# violed_v2_5.net
KiCad netlist of a schematic drawn in EAGLE
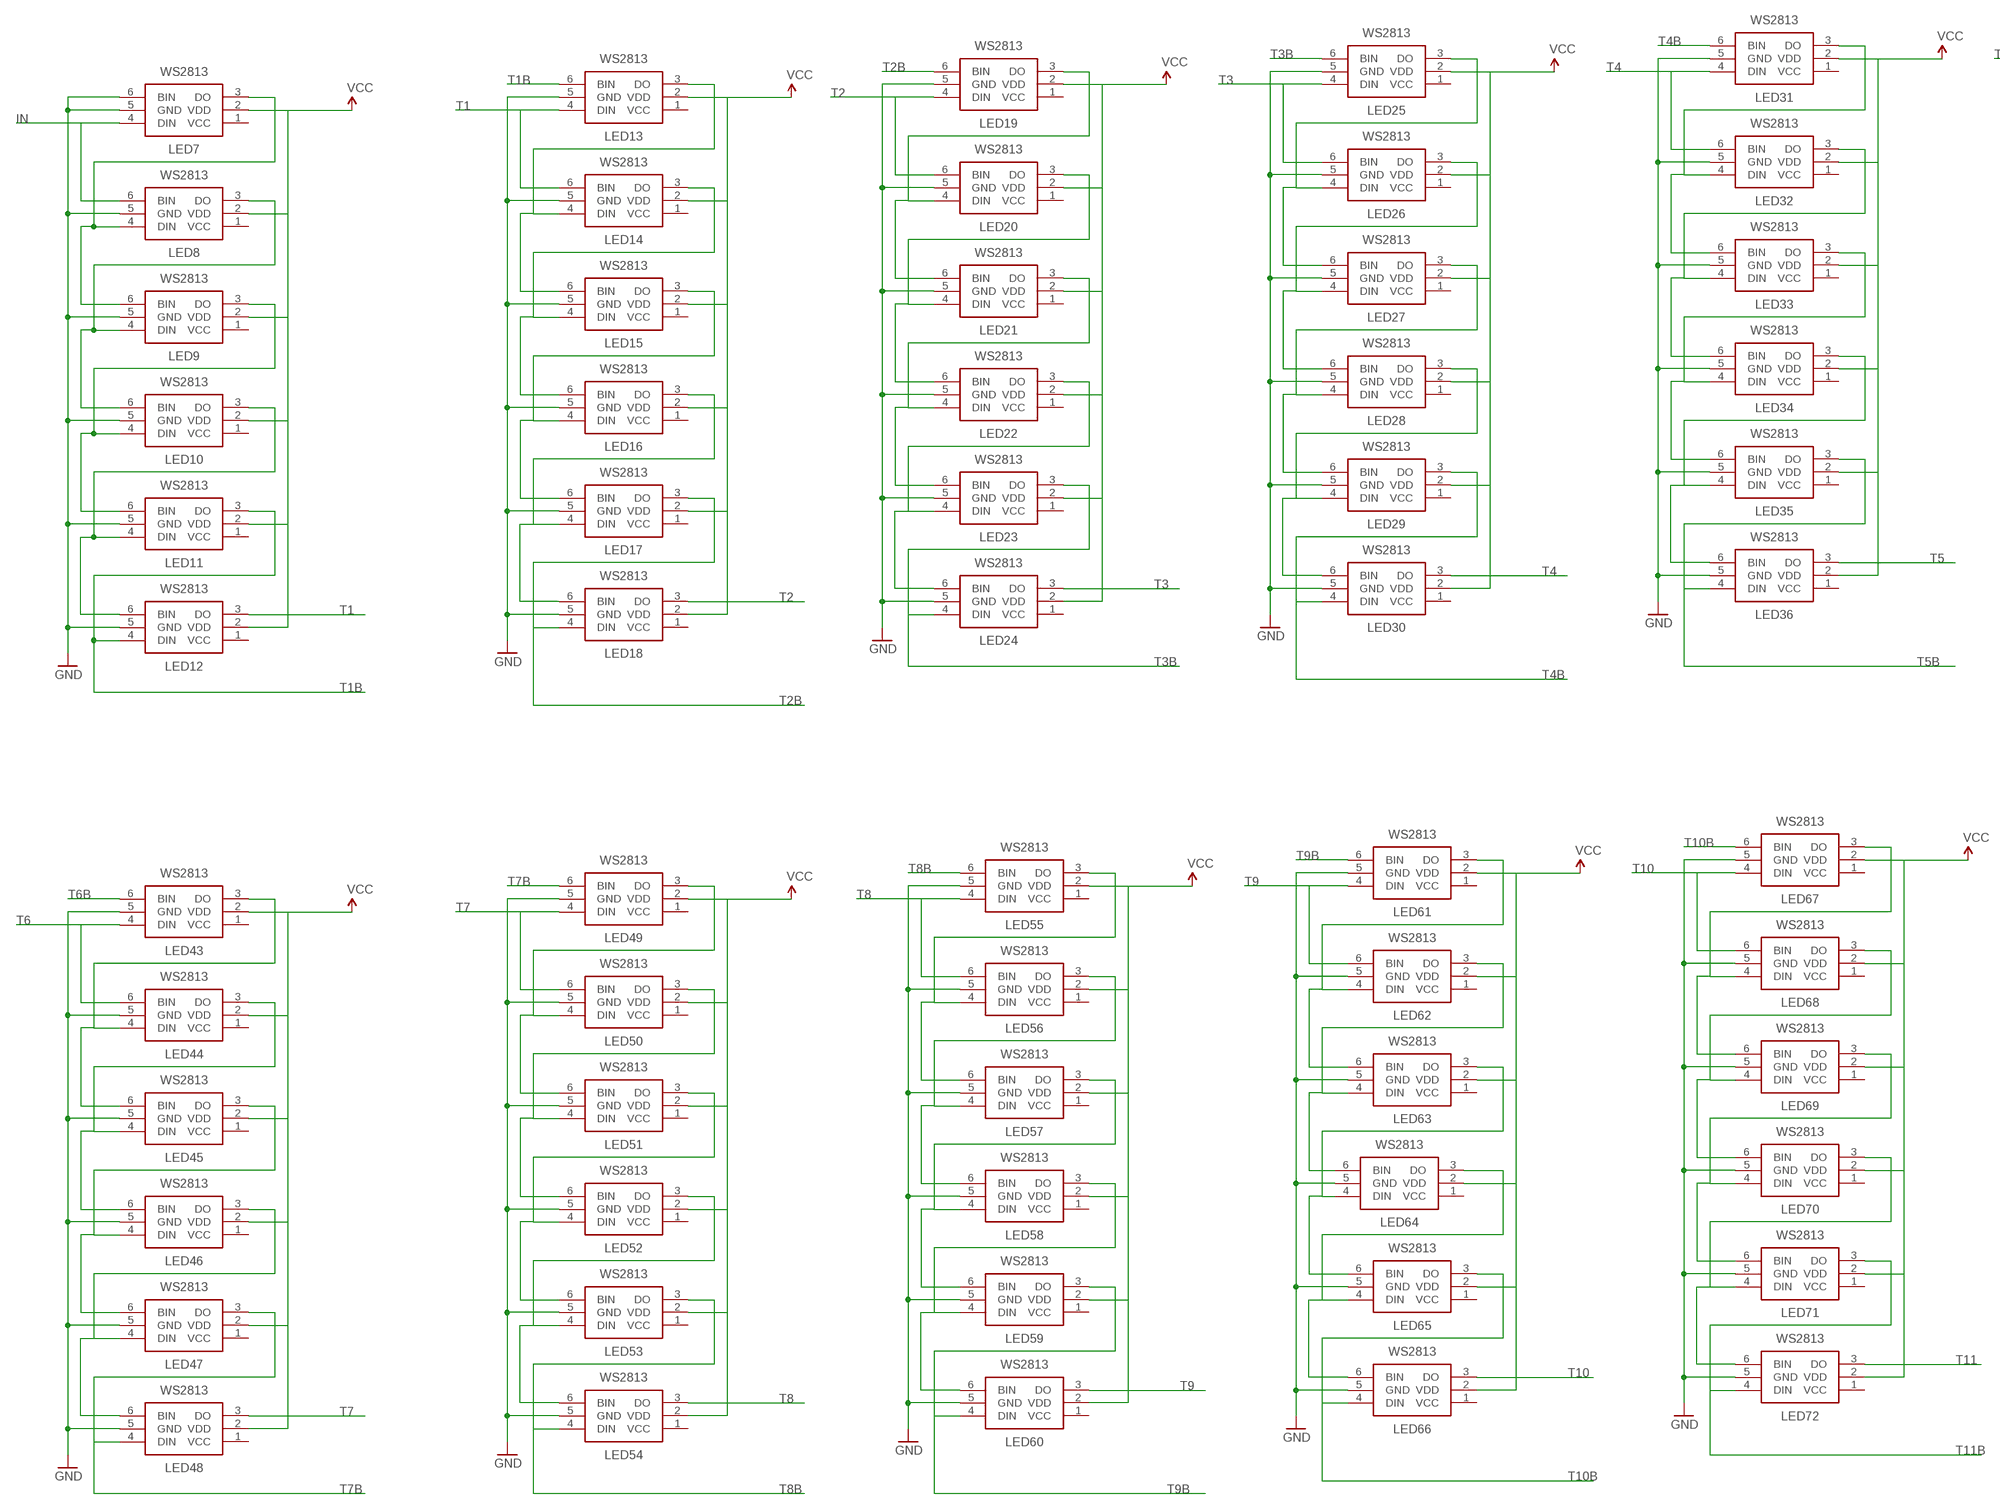
[diagram p0: schematic, sheet 1, part 1 of 2]
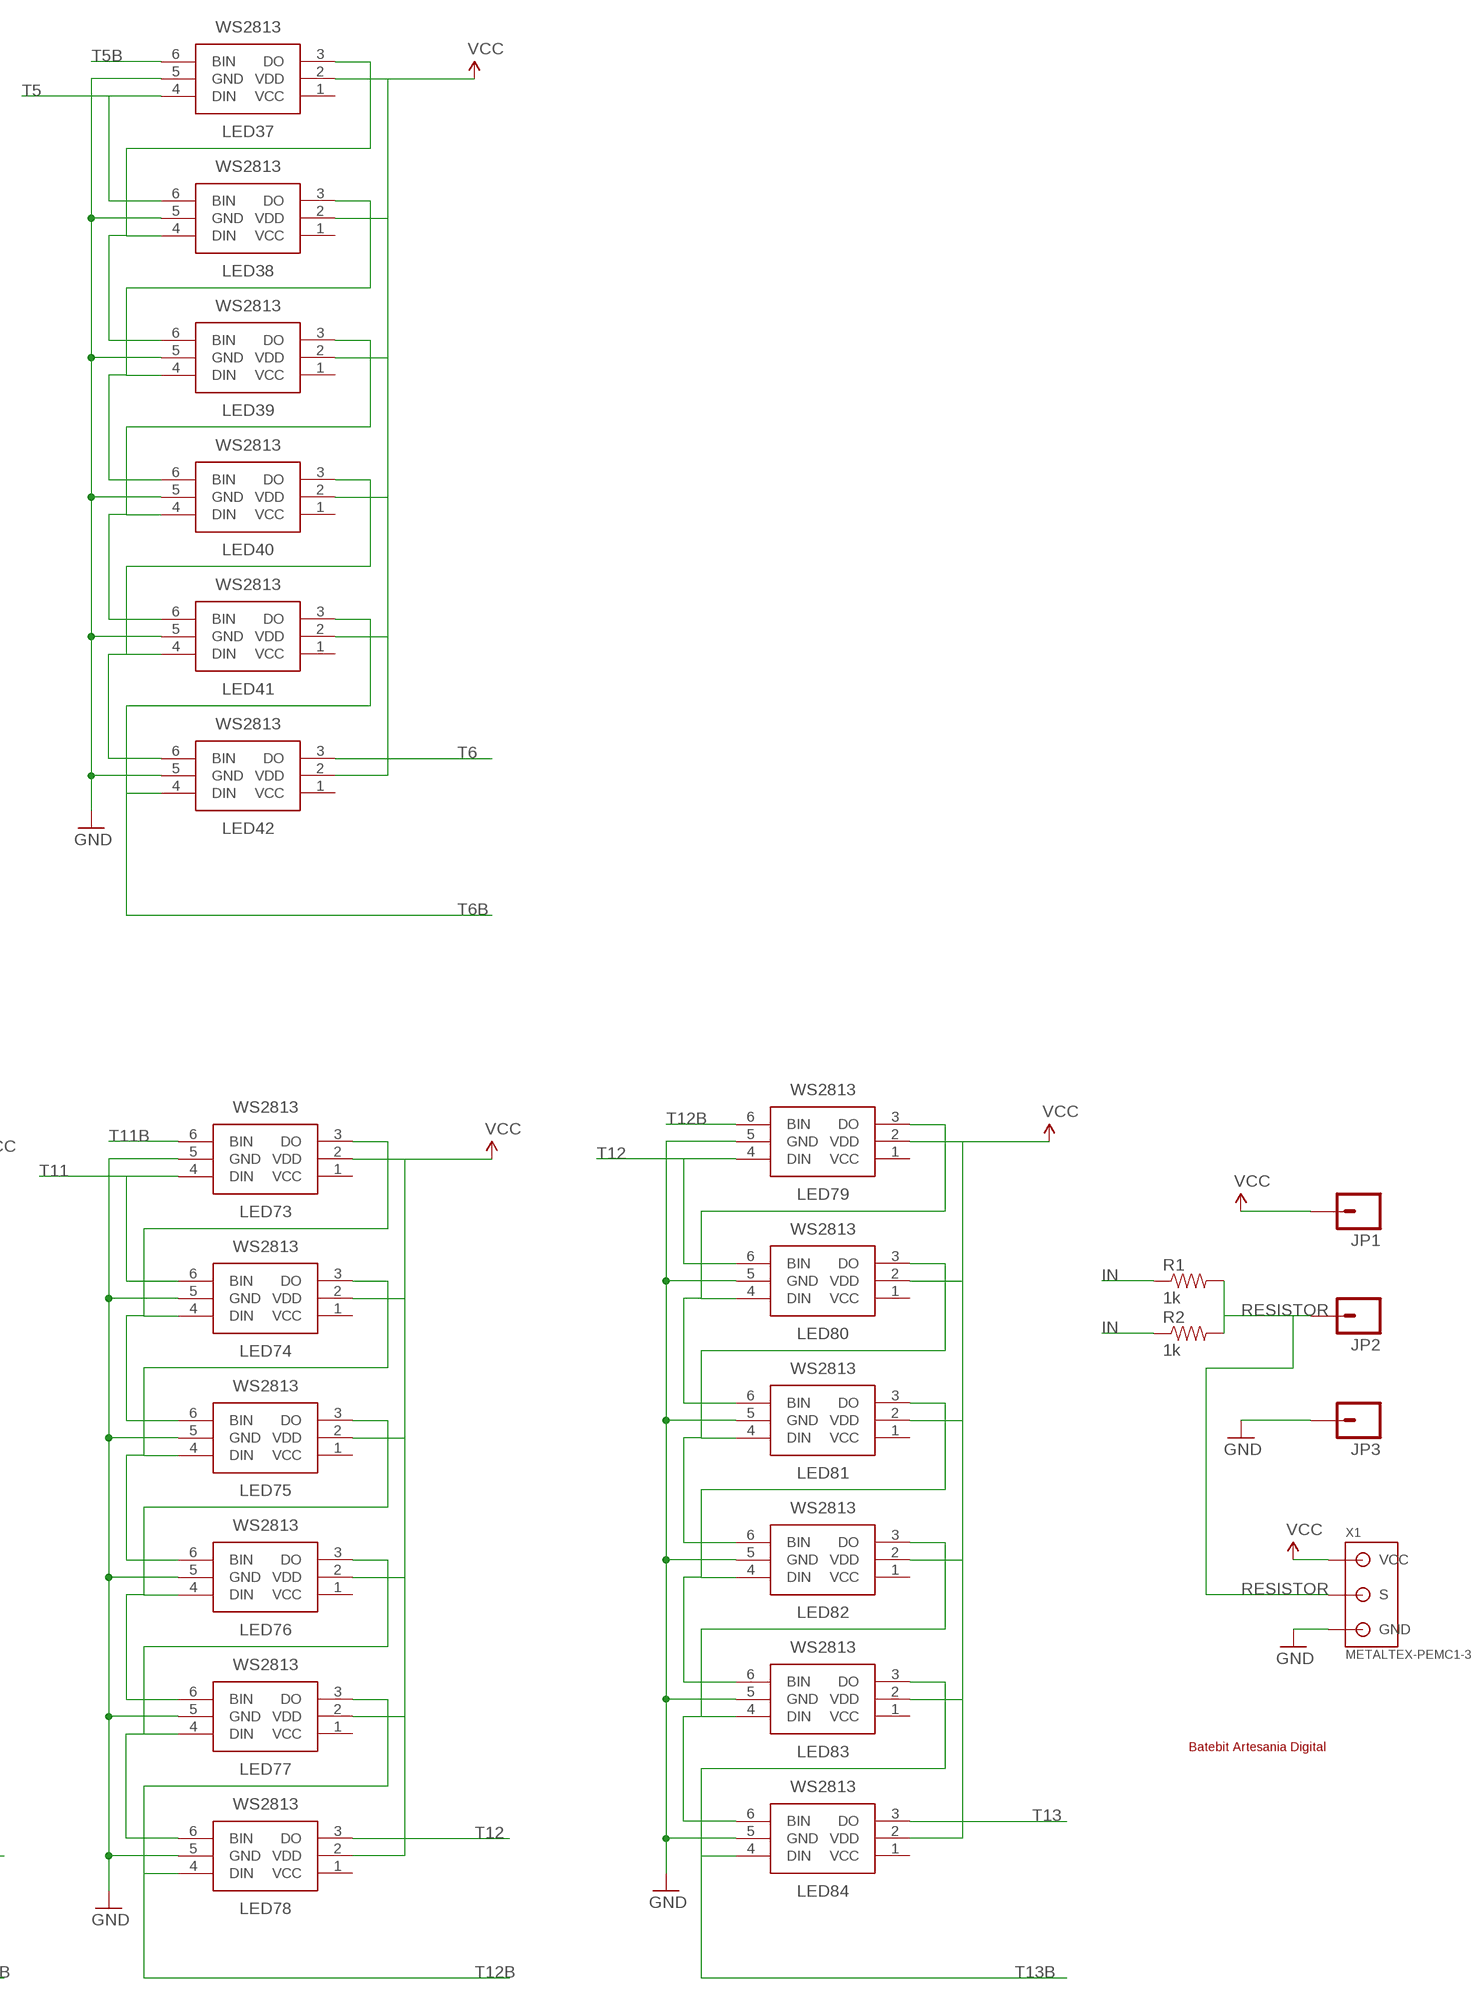
[diagram p1: schematic, sheet 1, part 2 of 2]

(export (version "E")
  (design (tool "Eeschema 10.0.6"))
  (components
    (comp (ref "JP1")
      (value "M01PTH_LONGPAD")
      (footprint "eagle-import:1X01_LONGPAD")
      (libsource (lib "eagle-import") (part "M01PTH_LONGPAD"))
    )
    (comp (ref "JP2")
      (value "M01PTH_LONGPAD")
      (footprint "eagle-import:1X01_LONGPAD")
      (libsource (lib "eagle-import") (part "M01PTH_LONGPAD"))
    )
    (comp (ref "JP3")
      (value "M01PTH_LONGPAD")
      (footprint "eagle-import:1X01_LONGPAD")
      (libsource (lib "eagle-import") (part "M01PTH_LONGPAD"))
    )
    (comp (ref "LED7")
      (value "WS2813")
      (footprint "eagle-import:WS2812")
      (libsource (lib "eagle-import") (part "WS2813"))
    )
    (comp (ref "LED8")
      (value "WS2813")
      (footprint "eagle-import:WS2812")
      (libsource (lib "eagle-import") (part "WS2813"))
    )
    (comp (ref "LED9")
      (value "WS2813")
      (footprint "eagle-import:WS2812")
      (libsource (lib "eagle-import") (part "WS2813"))
    )
    (comp (ref "LED10")
      (value "WS2813")
      (footprint "eagle-import:WS2812")
      (libsource (lib "eagle-import") (part "WS2813"))
    )
    (comp (ref "LED11")
      (value "WS2813")
      (footprint "eagle-import:WS2812")
      (libsource (lib "eagle-import") (part "WS2813"))
    )
    (comp (ref "LED12")
      (value "WS2813")
      (footprint "eagle-import:WS2812")
      (libsource (lib "eagle-import") (part "WS2813"))
    )
    (comp (ref "LED13")
      (value "WS2813")
      (footprint "eagle-import:WS2812")
      (libsource (lib "eagle-import") (part "WS2813"))
    )
    (comp (ref "LED14")
      (value "WS2813")
      (footprint "eagle-import:WS2812")
      (libsource (lib "eagle-import") (part "WS2813"))
    )
    (comp (ref "LED15")
      (value "WS2813")
      (footprint "eagle-import:WS2812")
      (libsource (lib "eagle-import") (part "WS2813"))
    )
    (comp (ref "LED16")
      (value "WS2813")
      (footprint "eagle-import:WS2812")
      (libsource (lib "eagle-import") (part "WS2813"))
    )
    (comp (ref "LED17")
      (value "WS2813")
      (footprint "eagle-import:WS2812")
      (libsource (lib "eagle-import") (part "WS2813"))
    )
    (comp (ref "LED18")
      (value "WS2813")
      (footprint "eagle-import:WS2812")
      (libsource (lib "eagle-import") (part "WS2813"))
    )
    (comp (ref "LED19")
      (value "WS2813")
      (footprint "eagle-import:WS2812")
      (libsource (lib "eagle-import") (part "WS2813"))
    )
    (comp (ref "LED20")
      (value "WS2813")
      (footprint "eagle-import:WS2812")
      (libsource (lib "eagle-import") (part "WS2813"))
    )
    (comp (ref "LED21")
      (value "WS2813")
      (footprint "eagle-import:WS2812")
      (libsource (lib "eagle-import") (part "WS2813"))
    )
    (comp (ref "LED22")
      (value "WS2813")
      (footprint "eagle-import:WS2812")
      (libsource (lib "eagle-import") (part "WS2813"))
    )
    (comp (ref "LED23")
      (value "WS2813")
      (footprint "eagle-import:WS2812")
      (libsource (lib "eagle-import") (part "WS2813"))
    )
    (comp (ref "LED24")
      (value "WS2813")
      (footprint "eagle-import:WS2812")
      (libsource (lib "eagle-import") (part "WS2813"))
    )
    (comp (ref "LED25")
      (value "WS2813")
      (footprint "eagle-import:WS2812")
      (libsource (lib "eagle-import") (part "WS2813"))
    )
    (comp (ref "LED26")
      (value "WS2813")
      (footprint "eagle-import:WS2812")
      (libsource (lib "eagle-import") (part "WS2813"))
    )
    (comp (ref "LED27")
      (value "WS2813")
      (footprint "eagle-import:WS2812")
      (libsource (lib "eagle-import") (part "WS2813"))
    )
    (comp (ref "LED28")
      (value "WS2813")
      (footprint "eagle-import:WS2812")
      (libsource (lib "eagle-import") (part "WS2813"))
    )
    (comp (ref "LED29")
      (value "WS2813")
      (footprint "eagle-import:WS2812")
      (libsource (lib "eagle-import") (part "WS2813"))
    )
    (comp (ref "LED30")
      (value "WS2813")
      (footprint "eagle-import:WS2812")
      (libsource (lib "eagle-import") (part "WS2813"))
    )
    (comp (ref "LED31")
      (value "WS2813")
      (footprint "eagle-import:WS2812")
      (libsource (lib "eagle-import") (part "WS2813"))
    )
    (comp (ref "LED32")
      (value "WS2813")
      (footprint "eagle-import:WS2812")
      (libsource (lib "eagle-import") (part "WS2813"))
    )
    (comp (ref "LED33")
      (value "WS2813")
      (footprint "eagle-import:WS2812")
      (libsource (lib "eagle-import") (part "WS2813"))
    )
    (comp (ref "LED34")
      (value "WS2813")
      (footprint "eagle-import:WS2812")
      (libsource (lib "eagle-import") (part "WS2813"))
    )
    (comp (ref "LED35")
      (value "WS2813")
      (footprint "eagle-import:WS2812")
      (libsource (lib "eagle-import") (part "WS2813"))
    )
    (comp (ref "LED36")
      (value "WS2813")
      (footprint "eagle-import:WS2812")
      (libsource (lib "eagle-import") (part "WS2813"))
    )
    (comp (ref "LED37")
      (value "WS2813")
      (footprint "eagle-import:WS2812")
      (libsource (lib "eagle-import") (part "WS2813"))
    )
    (comp (ref "LED38")
      (value "WS2813")
      (footprint "eagle-import:WS2812")
      (libsource (lib "eagle-import") (part "WS2813"))
    )
    (comp (ref "LED39")
      (value "WS2813")
      (footprint "eagle-import:WS2812")
      (libsource (lib "eagle-import") (part "WS2813"))
    )
    (comp (ref "LED40")
      (value "WS2813")
      (footprint "eagle-import:WS2812")
      (libsource (lib "eagle-import") (part "WS2813"))
    )
    (comp (ref "LED41")
      (value "WS2813")
      (footprint "eagle-import:WS2812")
      (libsource (lib "eagle-import") (part "WS2813"))
    )
    (comp (ref "LED42")
      (value "WS2813")
      (footprint "eagle-import:WS2812")
      (libsource (lib "eagle-import") (part "WS2813"))
    )
    (comp (ref "LED43")
      (value "WS2813")
      (footprint "eagle-import:WS2812")
      (libsource (lib "eagle-import") (part "WS2813"))
    )
    (comp (ref "LED44")
      (value "WS2813")
      (footprint "eagle-import:WS2812")
      (libsource (lib "eagle-import") (part "WS2813"))
    )
    (comp (ref "LED45")
      (value "WS2813")
      (footprint "eagle-import:WS2812")
      (libsource (lib "eagle-import") (part "WS2813"))
    )
    (comp (ref "LED46")
      (value "WS2813")
      (footprint "eagle-import:WS2812")
      (libsource (lib "eagle-import") (part "WS2813"))
    )
    (comp (ref "LED47")
      (value "WS2813")
      (footprint "eagle-import:WS2812")
      (libsource (lib "eagle-import") (part "WS2813"))
    )
    (comp (ref "LED48")
      (value "WS2813")
      (footprint "eagle-import:WS2812")
      (libsource (lib "eagle-import") (part "WS2813"))
    )
    (comp (ref "LED49")
      (value "WS2813")
      (footprint "eagle-import:WS2812")
      (libsource (lib "eagle-import") (part "WS2813"))
    )
    (comp (ref "LED50")
      (value "WS2813")
      (footprint "eagle-import:WS2812")
      (libsource (lib "eagle-import") (part "WS2813"))
    )
    (comp (ref "LED51")
      (value "WS2813")
      (footprint "eagle-import:WS2812")
      (libsource (lib "eagle-import") (part "WS2813"))
    )
    (comp (ref "LED52")
      (value "WS2813")
      (footprint "eagle-import:WS2812")
      (libsource (lib "eagle-import") (part "WS2813"))
    )
    (comp (ref "LED53")
      (value "WS2813")
      (footprint "eagle-import:WS2812")
      (libsource (lib "eagle-import") (part "WS2813"))
    )
    (comp (ref "LED54")
      (value "WS2813")
      (footprint "eagle-import:WS2812")
      (libsource (lib "eagle-import") (part "WS2813"))
    )
    (comp (ref "LED55")
      (value "WS2813")
      (footprint "eagle-import:WS2812")
      (libsource (lib "eagle-import") (part "WS2813"))
    )
    (comp (ref "LED56")
      (value "WS2813")
      (footprint "eagle-import:WS2812")
      (libsource (lib "eagle-import") (part "WS2813"))
    )
    (comp (ref "LED57")
      (value "WS2813")
      (footprint "eagle-import:WS2812")
      (libsource (lib "eagle-import") (part "WS2813"))
    )
    (comp (ref "LED58")
      (value "WS2813")
      (footprint "eagle-import:WS2812")
      (libsource (lib "eagle-import") (part "WS2813"))
    )
    (comp (ref "LED59")
      (value "WS2813")
      (footprint "eagle-import:WS2812")
      (libsource (lib "eagle-import") (part "WS2813"))
    )
    (comp (ref "LED60")
      (value "WS2813")
      (footprint "eagle-import:WS2812")
      (libsource (lib "eagle-import") (part "WS2813"))
    )
    (comp (ref "LED61")
      (value "WS2813")
      (footprint "eagle-import:WS2812")
      (libsource (lib "eagle-import") (part "WS2813"))
    )
    (comp (ref "LED62")
      (value "WS2813")
      (footprint "eagle-import:WS2812")
      (libsource (lib "eagle-import") (part "WS2813"))
    )
    (comp (ref "LED63")
      (value "WS2813")
      (footprint "eagle-import:WS2812")
      (libsource (lib "eagle-import") (part "WS2813"))
    )
    (comp (ref "LED64")
      (value "WS2813")
      (footprint "eagle-import:WS2812")
      (libsource (lib "eagle-import") (part "WS2813"))
    )
    (comp (ref "LED65")
      (value "WS2813")
      (footprint "eagle-import:WS2812")
      (libsource (lib "eagle-import") (part "WS2813"))
    )
    (comp (ref "LED66")
      (value "WS2813")
      (footprint "eagle-import:WS2812")
      (libsource (lib "eagle-import") (part "WS2813"))
    )
    (comp (ref "LED67")
      (value "WS2813")
      (footprint "eagle-import:WS2812")
      (libsource (lib "eagle-import") (part "WS2813"))
    )
    (comp (ref "LED68")
      (value "WS2813")
      (footprint "eagle-import:WS2812")
      (libsource (lib "eagle-import") (part "WS2813"))
    )
    (comp (ref "LED69")
      (value "WS2813")
      (footprint "eagle-import:WS2812")
      (libsource (lib "eagle-import") (part "WS2813"))
    )
    (comp (ref "LED70")
      (value "WS2813")
      (footprint "eagle-import:WS2812")
      (libsource (lib "eagle-import") (part "WS2813"))
    )
    (comp (ref "LED71")
      (value "WS2813")
      (footprint "eagle-import:WS2812")
      (libsource (lib "eagle-import") (part "WS2813"))
    )
    (comp (ref "LED72")
      (value "WS2813")
      (footprint "eagle-import:WS2812")
      (libsource (lib "eagle-import") (part "WS2813"))
    )
    (comp (ref "LED73")
      (value "WS2813")
      (footprint "eagle-import:WS2812")
      (libsource (lib "eagle-import") (part "WS2813"))
    )
    (comp (ref "LED74")
      (value "WS2813")
      (footprint "eagle-import:WS2812")
      (libsource (lib "eagle-import") (part "WS2813"))
    )
    (comp (ref "LED75")
      (value "WS2813")
      (footprint "eagle-import:WS2812")
      (libsource (lib "eagle-import") (part "WS2813"))
    )
    (comp (ref "LED76")
      (value "WS2813")
      (footprint "eagle-import:WS2812")
      (libsource (lib "eagle-import") (part "WS2813"))
    )
    (comp (ref "LED77")
      (value "WS2813")
      (footprint "eagle-import:WS2812")
      (libsource (lib "eagle-import") (part "WS2813"))
    )
    (comp (ref "LED78")
      (value "WS2813")
      (footprint "eagle-import:WS2812")
      (libsource (lib "eagle-import") (part "WS2813"))
    )
    (comp (ref "LED79")
      (value "WS2813")
      (footprint "eagle-import:WS2812")
      (libsource (lib "eagle-import") (part "WS2813"))
    )
    (comp (ref "LED80")
      (value "WS2813")
      (footprint "eagle-import:WS2812")
      (libsource (lib "eagle-import") (part "WS2813"))
    )
    (comp (ref "LED81")
      (value "WS2813")
      (footprint "eagle-import:WS2812")
      (libsource (lib "eagle-import") (part "WS2813"))
    )
    (comp (ref "LED82")
      (value "WS2813")
      (footprint "eagle-import:WS2812")
      (libsource (lib "eagle-import") (part "WS2813"))
    )
    (comp (ref "LED83")
      (value "WS2813")
      (footprint "eagle-import:WS2812")
      (libsource (lib "eagle-import") (part "WS2813"))
    )
    (comp (ref "LED84")
      (value "WS2813")
      (footprint "eagle-import:WS2812")
      (libsource (lib "eagle-import") (part "WS2813"))
    )
    (comp (ref "R1")
      (value "1k")
      (footprint "eagle-import:0805")
      (libsource (lib "eagle-import") (part "RESISTOR0805-RES"))
    )
    (comp (ref "R2")
      (value "1k")
      (footprint "eagle-import:AXIAL-0.4")
      (libsource (lib "eagle-import") (part "RESISTORPTH-1/4W"))
    )
    (comp (ref "U$1")
      (value "BATEBITTOP")
      (footprint "eagle-import:BATEBIT_MED_TOP_LAYER")
      (libsource (lib "eagle-import") (part "BATEBITTOP"))
    )
    (comp (ref "X1")
      (value "METALTEX-PEMC1-3")
      (footprint "eagle-import:METALTEX-PEMC1-3-PACKAGE-LONG-PAD")
      (libsource (lib "eagle-import") (part "METALTEX-PEMC1-3"))
    )
  )
  (nets
    (net (code "1") (name "/IN") (class "Default")
      (node (ref "LED7") (pin "4") (pinfunction "DIN_4") (pintype "passive"))
      (node (ref "LED8") (pin "6") (pinfunction "BIN_6") (pintype "passive"))
      (node (ref "R1") (pin "1") (pinfunction "1_1") (pintype "passive"))
      (node (ref "R2") (pin "P$1") (pinfunction "1_P$1") (pintype "passive"))
    )
    (net (code "2") (name "/RESISTOR") (class "Default")
      (node (ref "JP2") (pin "1") (pinfunction "1_1") (pintype "passive"))
      (node (ref "R1") (pin "2") (pinfunction "2_2") (pintype "passive"))
      (node (ref "R2") (pin "P$2") (pinfunction "2_P$2") (pintype "passive"))
      (node (ref "X1") (pin "2") (pinfunction "S_2") (pintype "bidirectional"))
    )
    (net (code "3") (name "/T1") (class "Default")
      (node (ref "LED12") (pin "3") (pinfunction "DO_3") (pintype "passive"))
      (node (ref "LED13") (pin "4") (pinfunction "DIN_4") (pintype "passive"))
      (node (ref "LED14") (pin "6") (pinfunction "BIN_6") (pintype "passive"))
    )
    (net (code "4") (name "/T1B") (class "Default")
      (node (ref "LED11") (pin "3") (pinfunction "DO_3") (pintype "passive"))
      (node (ref "LED12") (pin "4") (pinfunction "DIN_4") (pintype "passive"))
      (node (ref "LED13") (pin "6") (pinfunction "BIN_6") (pintype "passive"))
    )
    (net (code "5") (name "/T2") (class "Default")
      (node (ref "LED18") (pin "3") (pinfunction "DO_3") (pintype "passive"))
      (node (ref "LED19") (pin "4") (pinfunction "DIN_4") (pintype "passive"))
      (node (ref "LED20") (pin "6") (pinfunction "BIN_6") (pintype "passive"))
    )
    (net (code "6") (name "/T2B") (class "Default")
      (node (ref "LED17") (pin "3") (pinfunction "DO_3") (pintype "passive"))
      (node (ref "LED18") (pin "4") (pinfunction "DIN_4") (pintype "passive"))
      (node (ref "LED19") (pin "6") (pinfunction "BIN_6") (pintype "passive"))
    )
    (net (code "7") (name "/T3") (class "Default")
      (node (ref "LED24") (pin "3") (pinfunction "DO_3") (pintype "passive"))
      (node (ref "LED25") (pin "4") (pinfunction "DIN_4") (pintype "passive"))
      (node (ref "LED26") (pin "6") (pinfunction "BIN_6") (pintype "passive"))
    )
    (net (code "8") (name "/T3B") (class "Default")
      (node (ref "LED23") (pin "3") (pinfunction "DO_3") (pintype "passive"))
      (node (ref "LED24") (pin "4") (pinfunction "DIN_4") (pintype "passive"))
      (node (ref "LED25") (pin "6") (pinfunction "BIN_6") (pintype "passive"))
    )
    (net (code "9") (name "/T4") (class "Default")
      (node (ref "LED30") (pin "3") (pinfunction "DO_3") (pintype "passive"))
      (node (ref "LED31") (pin "4") (pinfunction "DIN_4") (pintype "passive"))
      (node (ref "LED32") (pin "6") (pinfunction "BIN_6") (pintype "passive"))
    )
    (net (code "10") (name "/T4B") (class "Default")
      (node (ref "LED29") (pin "3") (pinfunction "DO_3") (pintype "passive"))
      (node (ref "LED30") (pin "4") (pinfunction "DIN_4") (pintype "passive"))
      (node (ref "LED31") (pin "6") (pinfunction "BIN_6") (pintype "passive"))
    )
    (net (code "11") (name "/T5") (class "Default")
      (node (ref "LED36") (pin "3") (pinfunction "DO_3") (pintype "passive"))
      (node (ref "LED37") (pin "4") (pinfunction "DIN_4") (pintype "passive"))
      (node (ref "LED38") (pin "6") (pinfunction "BIN_6") (pintype "passive"))
    )
    (net (code "12") (name "/T5B") (class "Default")
      (node (ref "LED35") (pin "3") (pinfunction "DO_3") (pintype "passive"))
      (node (ref "LED36") (pin "4") (pinfunction "DIN_4") (pintype "passive"))
      (node (ref "LED37") (pin "6") (pinfunction "BIN_6") (pintype "passive"))
    )
    (net (code "13") (name "/T6") (class "Default")
      (node (ref "LED42") (pin "3") (pinfunction "DO_3") (pintype "passive"))
      (node (ref "LED43") (pin "4") (pinfunction "DIN_4") (pintype "passive"))
      (node (ref "LED44") (pin "6") (pinfunction "BIN_6") (pintype "passive"))
    )
    (net (code "14") (name "/T6B") (class "Default")
      (node (ref "LED41") (pin "3") (pinfunction "DO_3") (pintype "passive"))
      (node (ref "LED42") (pin "4") (pinfunction "DIN_4") (pintype "passive"))
      (node (ref "LED43") (pin "6") (pinfunction "BIN_6") (pintype "passive"))
    )
    (net (code "15") (name "/T7") (class "Default")
      (node (ref "LED48") (pin "3") (pinfunction "DO_3") (pintype "passive"))
      (node (ref "LED49") (pin "4") (pinfunction "DIN_4") (pintype "passive"))
      (node (ref "LED50") (pin "6") (pinfunction "BIN_6") (pintype "passive"))
    )
    (net (code "16") (name "/T7B") (class "Default")
      (node (ref "LED47") (pin "3") (pinfunction "DO_3") (pintype "passive"))
      (node (ref "LED48") (pin "4") (pinfunction "DIN_4") (pintype "passive"))
      (node (ref "LED49") (pin "6") (pinfunction "BIN_6") (pintype "passive"))
    )
    (net (code "17") (name "/T8") (class "Default")
      (node (ref "LED54") (pin "3") (pinfunction "DO_3") (pintype "passive"))
      (node (ref "LED55") (pin "4") (pinfunction "DIN_4") (pintype "passive"))
      (node (ref "LED56") (pin "6") (pinfunction "BIN_6") (pintype "passive"))
    )
    (net (code "18") (name "/T8B") (class "Default")
      (node (ref "LED53") (pin "3") (pinfunction "DO_3") (pintype "passive"))
      (node (ref "LED54") (pin "4") (pinfunction "DIN_4") (pintype "passive"))
      (node (ref "LED55") (pin "6") (pinfunction "BIN_6") (pintype "passive"))
    )
    (net (code "19") (name "/T9") (class "Default")
      (node (ref "LED60") (pin "3") (pinfunction "DO_3") (pintype "passive"))
      (node (ref "LED61") (pin "4") (pinfunction "DIN_4") (pintype "passive"))
      (node (ref "LED62") (pin "6") (pinfunction "BIN_6") (pintype "passive"))
    )
    (net (code "20") (name "/T9B") (class "Default")
      (node (ref "LED59") (pin "3") (pinfunction "DO_3") (pintype "passive"))
      (node (ref "LED60") (pin "4") (pinfunction "DIN_4") (pintype "passive"))
      (node (ref "LED61") (pin "6") (pinfunction "BIN_6") (pintype "passive"))
    )
    (net (code "21") (name "/T10") (class "Default")
      (node (ref "LED66") (pin "3") (pinfunction "DO_3") (pintype "passive"))
      (node (ref "LED67") (pin "4") (pinfunction "DIN_4") (pintype "passive"))
      (node (ref "LED68") (pin "6") (pinfunction "BIN_6") (pintype "passive"))
    )
    (net (code "22") (name "/T10B") (class "Default")
      (node (ref "LED65") (pin "3") (pinfunction "DO_3") (pintype "passive"))
      (node (ref "LED66") (pin "4") (pinfunction "DIN_4") (pintype "passive"))
      (node (ref "LED67") (pin "6") (pinfunction "BIN_6") (pintype "passive"))
    )
    (net (code "23") (name "/T11") (class "Default")
      (node (ref "LED72") (pin "3") (pinfunction "DO_3") (pintype "passive"))
      (node (ref "LED73") (pin "4") (pinfunction "DIN_4") (pintype "passive"))
      (node (ref "LED74") (pin "6") (pinfunction "BIN_6") (pintype "passive"))
    )
    (net (code "24") (name "/T11B") (class "Default")
      (node (ref "LED71") (pin "3") (pinfunction "DO_3") (pintype "passive"))
      (node (ref "LED72") (pin "4") (pinfunction "DIN_4") (pintype "passive"))
      (node (ref "LED73") (pin "6") (pinfunction "BIN_6") (pintype "passive"))
    )
    (net (code "25") (name "/T12") (class "Default")
      (node (ref "LED78") (pin "3") (pinfunction "DO_3") (pintype "passive"))
      (node (ref "LED79") (pin "4") (pinfunction "DIN_4") (pintype "passive"))
      (node (ref "LED80") (pin "6") (pinfunction "BIN_6") (pintype "passive"))
    )
    (net (code "26") (name "/T12B") (class "Default")
      (node (ref "LED77") (pin "3") (pinfunction "DO_3") (pintype "passive"))
      (node (ref "LED78") (pin "4") (pinfunction "DIN_4") (pintype "passive"))
      (node (ref "LED79") (pin "6") (pinfunction "BIN_6") (pintype "passive"))
    )
    (net (code "27") (name "/T13") (class "Default")
      (node (ref "LED84") (pin "3") (pinfunction "DO_3") (pintype "passive"))
    )
    (net (code "28") (name "/T13B") (class "Default")
      (node (ref "LED83") (pin "3") (pinfunction "DO_3") (pintype "passive"))
      (node (ref "LED84") (pin "4") (pinfunction "DIN_4") (pintype "passive"))
    )
    (net (code "29") (name "GND") (class "Default")
      (node (ref "JP3") (pin "1") (pinfunction "1_1") (pintype "passive"))
      (node (ref "LED10") (pin "5") (pinfunction "GND_5") (pintype "passive"))
      (node (ref "LED11") (pin "5") (pinfunction "GND_5") (pintype "passive"))
      (node (ref "LED12") (pin "5") (pinfunction "GND_5") (pintype "passive"))
      (node (ref "LED13") (pin "5") (pinfunction "GND_5") (pintype "passive"))
      (node (ref "LED14") (pin "5") (pinfunction "GND_5") (pintype "passive"))
      (node (ref "LED15") (pin "5") (pinfunction "GND_5") (pintype "passive"))
      (node (ref "LED16") (pin "5") (pinfunction "GND_5") (pintype "passive"))
      (node (ref "LED17") (pin "5") (pinfunction "GND_5") (pintype "passive"))
      (node (ref "LED18") (pin "5") (pinfunction "GND_5") (pintype "passive"))
      (node (ref "LED19") (pin "5") (pinfunction "GND_5") (pintype "passive"))
      (node (ref "LED20") (pin "5") (pinfunction "GND_5") (pintype "passive"))
      (node (ref "LED21") (pin "5") (pinfunction "GND_5") (pintype "passive"))
      (node (ref "LED22") (pin "5") (pinfunction "GND_5") (pintype "passive"))
      (node (ref "LED23") (pin "5") (pinfunction "GND_5") (pintype "passive"))
      (node (ref "LED24") (pin "5") (pinfunction "GND_5") (pintype "passive"))
      (node (ref "LED25") (pin "5") (pinfunction "GND_5") (pintype "passive"))
      (node (ref "LED26") (pin "5") (pinfunction "GND_5") (pintype "passive"))
      (node (ref "LED27") (pin "5") (pinfunction "GND_5") (pintype "passive"))
      (node (ref "LED28") (pin "5") (pinfunction "GND_5") (pintype "passive"))
      (node (ref "LED29") (pin "5") (pinfunction "GND_5") (pintype "passive"))
      (node (ref "LED30") (pin "5") (pinfunction "GND_5") (pintype "passive"))
      (node (ref "LED31") (pin "5") (pinfunction "GND_5") (pintype "passive"))
      (node (ref "LED32") (pin "5") (pinfunction "GND_5") (pintype "passive"))
      (node (ref "LED33") (pin "5") (pinfunction "GND_5") (pintype "passive"))
      (node (ref "LED34") (pin "5") (pinfunction "GND_5") (pintype "passive"))
      (node (ref "LED35") (pin "5") (pinfunction "GND_5") (pintype "passive"))
      (node (ref "LED36") (pin "5") (pinfunction "GND_5") (pintype "passive"))
      (node (ref "LED37") (pin "5") (pinfunction "GND_5") (pintype "passive"))
      (node (ref "LED38") (pin "5") (pinfunction "GND_5") (pintype "passive"))
      (node (ref "LED39") (pin "5") (pinfunction "GND_5") (pintype "passive"))
      (node (ref "LED40") (pin "5") (pinfunction "GND_5") (pintype "passive"))
      (node (ref "LED41") (pin "5") (pinfunction "GND_5") (pintype "passive"))
      (node (ref "LED42") (pin "5") (pinfunction "GND_5") (pintype "passive"))
      (node (ref "LED43") (pin "5") (pinfunction "GND_5") (pintype "passive"))
      (node (ref "LED44") (pin "5") (pinfunction "GND_5") (pintype "passive"))
      (node (ref "LED45") (pin "5") (pinfunction "GND_5") (pintype "passive"))
      (node (ref "LED46") (pin "5") (pinfunction "GND_5") (pintype "passive"))
      (node (ref "LED47") (pin "5") (pinfunction "GND_5") (pintype "passive"))
      (node (ref "LED48") (pin "5") (pinfunction "GND_5") (pintype "passive"))
      (node (ref "LED49") (pin "5") (pinfunction "GND_5") (pintype "passive"))
      (node (ref "LED50") (pin "5") (pinfunction "GND_5") (pintype "passive"))
      (node (ref "LED51") (pin "5") (pinfunction "GND_5") (pintype "passive"))
      (node (ref "LED52") (pin "5") (pinfunction "GND_5") (pintype "passive"))
      (node (ref "LED53") (pin "5") (pinfunction "GND_5") (pintype "passive"))
      (node (ref "LED54") (pin "5") (pinfunction "GND_5") (pintype "passive"))
      (node (ref "LED55") (pin "5") (pinfunction "GND_5") (pintype "passive"))
      (node (ref "LED56") (pin "5") (pinfunction "GND_5") (pintype "passive"))
      (node (ref "LED57") (pin "5") (pinfunction "GND_5") (pintype "passive"))
      (node (ref "LED58") (pin "5") (pinfunction "GND_5") (pintype "passive"))
      (node (ref "LED59") (pin "5") (pinfunction "GND_5") (pintype "passive"))
      (node (ref "LED60") (pin "5") (pinfunction "GND_5") (pintype "passive"))
      (node (ref "LED61") (pin "5") (pinfunction "GND_5") (pintype "passive"))
      (node (ref "LED62") (pin "5") (pinfunction "GND_5") (pintype "passive"))
      (node (ref "LED63") (pin "5") (pinfunction "GND_5") (pintype "passive"))
      (node (ref "LED64") (pin "5") (pinfunction "GND_5") (pintype "passive"))
      (node (ref "LED65") (pin "5") (pinfunction "GND_5") (pintype "passive"))
      (node (ref "LED66") (pin "5") (pinfunction "GND_5") (pintype "passive"))
      (node (ref "LED67") (pin "5") (pinfunction "GND_5") (pintype "passive"))
      (node (ref "LED68") (pin "5") (pinfunction "GND_5") (pintype "passive"))
      (node (ref "LED69") (pin "5") (pinfunction "GND_5") (pintype "passive"))
      (node (ref "LED7") (pin "5") (pinfunction "GND_5") (pintype "passive"))
      (node (ref "LED7") (pin "6") (pinfunction "BIN_6") (pintype "passive"))
      (node (ref "LED70") (pin "5") (pinfunction "GND_5") (pintype "passive"))
      (node (ref "LED71") (pin "5") (pinfunction "GND_5") (pintype "passive"))
      (node (ref "LED72") (pin "5") (pinfunction "GND_5") (pintype "passive"))
      (node (ref "LED73") (pin "5") (pinfunction "GND_5") (pintype "passive"))
      (node (ref "LED74") (pin "5") (pinfunction "GND_5") (pintype "passive"))
      (node (ref "LED75") (pin "5") (pinfunction "GND_5") (pintype "passive"))
      (node (ref "LED76") (pin "5") (pinfunction "GND_5") (pintype "passive"))
      (node (ref "LED77") (pin "5") (pinfunction "GND_5") (pintype "passive"))
      (node (ref "LED78") (pin "5") (pinfunction "GND_5") (pintype "passive"))
      (node (ref "LED79") (pin "5") (pinfunction "GND_5") (pintype "passive"))
      (node (ref "LED8") (pin "5") (pinfunction "GND_5") (pintype "passive"))
      (node (ref "LED80") (pin "5") (pinfunction "GND_5") (pintype "passive"))
      (node (ref "LED81") (pin "5") (pinfunction "GND_5") (pintype "passive"))
      (node (ref "LED82") (pin "5") (pinfunction "GND_5") (pintype "passive"))
      (node (ref "LED83") (pin "5") (pinfunction "GND_5") (pintype "passive"))
      (node (ref "LED84") (pin "5") (pinfunction "GND_5") (pintype "passive"))
      (node (ref "LED9") (pin "5") (pinfunction "GND_5") (pintype "passive"))
      (node (ref "X1") (pin "1") (pinfunction "GND_1") (pintype "bidirectional"))
    )
    (net (code "30") (name "Net-(LED7-DO)") (class "Default")
      (node (ref "LED7") (pin "3") (pinfunction "DO_3") (pintype "passive"))
      (node (ref "LED8") (pin "4") (pinfunction "DIN_4") (pintype "passive"))
      (node (ref "LED9") (pin "6") (pinfunction "BIN_6") (pintype "passive"))
    )
    (net (code "31") (name "Net-(LED10-BIN)") (class "Default")
      (node (ref "LED10") (pin "6") (pinfunction "BIN_6") (pintype "passive"))
      (node (ref "LED8") (pin "3") (pinfunction "DO_3") (pintype "passive"))
      (node (ref "LED9") (pin "4") (pinfunction "DIN_4") (pintype "passive"))
    )
    (net (code "32") (name "Net-(LED10-DIN)") (class "Default")
      (node (ref "LED10") (pin "4") (pinfunction "DIN_4") (pintype "passive"))
      (node (ref "LED11") (pin "6") (pinfunction "BIN_6") (pintype "passive"))
      (node (ref "LED9") (pin "3") (pinfunction "DO_3") (pintype "passive"))
    )
    (net (code "33") (name "Net-(LED10-DO)") (class "Default")
      (node (ref "LED10") (pin "3") (pinfunction "DO_3") (pintype "passive"))
      (node (ref "LED11") (pin "4") (pinfunction "DIN_4") (pintype "passive"))
      (node (ref "LED12") (pin "6") (pinfunction "BIN_6") (pintype "passive"))
    )
    (net (code "34") (name "Net-(LED13-DO)") (class "Default")
      (node (ref "LED13") (pin "3") (pinfunction "DO_3") (pintype "passive"))
      (node (ref "LED14") (pin "4") (pinfunction "DIN_4") (pintype "passive"))
      (node (ref "LED15") (pin "6") (pinfunction "BIN_6") (pintype "passive"))
    )
    (net (code "35") (name "Net-(LED14-DO)") (class "Default")
      (node (ref "LED14") (pin "3") (pinfunction "DO_3") (pintype "passive"))
      (node (ref "LED15") (pin "4") (pinfunction "DIN_4") (pintype "passive"))
      (node (ref "LED16") (pin "6") (pinfunction "BIN_6") (pintype "passive"))
    )
    (net (code "36") (name "Net-(LED15-DO)") (class "Default")
      (node (ref "LED15") (pin "3") (pinfunction "DO_3") (pintype "passive"))
      (node (ref "LED16") (pin "4") (pinfunction "DIN_4") (pintype "passive"))
      (node (ref "LED17") (pin "6") (pinfunction "BIN_6") (pintype "passive"))
    )
    (net (code "37") (name "Net-(LED16-DO)") (class "Default")
      (node (ref "LED16") (pin "3") (pinfunction "DO_3") (pintype "passive"))
      (node (ref "LED17") (pin "4") (pinfunction "DIN_4") (pintype "passive"))
      (node (ref "LED18") (pin "6") (pinfunction "BIN_6") (pintype "passive"))
    )
    (net (code "38") (name "Net-(LED19-DO)") (class "Default")
      (node (ref "LED19") (pin "3") (pinfunction "DO_3") (pintype "passive"))
      (node (ref "LED20") (pin "4") (pinfunction "DIN_4") (pintype "passive"))
      (node (ref "LED21") (pin "6") (pinfunction "BIN_6") (pintype "passive"))
    )
    (net (code "39") (name "Net-(LED20-DO)") (class "Default")
      (node (ref "LED20") (pin "3") (pinfunction "DO_3") (pintype "passive"))
      (node (ref "LED21") (pin "4") (pinfunction "DIN_4") (pintype "passive"))
      (node (ref "LED22") (pin "6") (pinfunction "BIN_6") (pintype "passive"))
    )
    (net (code "40") (name "Net-(LED21-DO)") (class "Default")
      (node (ref "LED21") (pin "3") (pinfunction "DO_3") (pintype "passive"))
      (node (ref "LED22") (pin "4") (pinfunction "DIN_4") (pintype "passive"))
      (node (ref "LED23") (pin "6") (pinfunction "BIN_6") (pintype "passive"))
    )
    (net (code "41") (name "Net-(LED22-DO)") (class "Default")
      (node (ref "LED22") (pin "3") (pinfunction "DO_3") (pintype "passive"))
      (node (ref "LED23") (pin "4") (pinfunction "DIN_4") (pintype "passive"))
      (node (ref "LED24") (pin "6") (pinfunction "BIN_6") (pintype "passive"))
    )
    (net (code "42") (name "Net-(LED25-DO)") (class "Default")
      (node (ref "LED25") (pin "3") (pinfunction "DO_3") (pintype "passive"))
      (node (ref "LED26") (pin "4") (pinfunction "DIN_4") (pintype "passive"))
      (node (ref "LED27") (pin "6") (pinfunction "BIN_6") (pintype "passive"))
    )
    (net (code "43") (name "Net-(LED26-DO)") (class "Default")
      (node (ref "LED26") (pin "3") (pinfunction "DO_3") (pintype "passive"))
      (node (ref "LED27") (pin "4") (pinfunction "DIN_4") (pintype "passive"))
      (node (ref "LED28") (pin "6") (pinfunction "BIN_6") (pintype "passive"))
    )
    (net (code "44") (name "Net-(LED27-DO)") (class "Default")
      (node (ref "LED27") (pin "3") (pinfunction "DO_3") (pintype "passive"))
      (node (ref "LED28") (pin "4") (pinfunction "DIN_4") (pintype "passive"))
      (node (ref "LED29") (pin "6") (pinfunction "BIN_6") (pintype "passive"))
    )
    (net (code "45") (name "Net-(LED28-DO)") (class "Default")
      (node (ref "LED28") (pin "3") (pinfunction "DO_3") (pintype "passive"))
      (node (ref "LED29") (pin "4") (pinfunction "DIN_4") (pintype "passive"))
      (node (ref "LED30") (pin "6") (pinfunction "BIN_6") (pintype "passive"))
    )
    (net (code "46") (name "Net-(LED31-DO)") (class "Default")
      (node (ref "LED31") (pin "3") (pinfunction "DO_3") (pintype "passive"))
      (node (ref "LED32") (pin "4") (pinfunction "DIN_4") (pintype "passive"))
      (node (ref "LED33") (pin "6") (pinfunction "BIN_6") (pintype "passive"))
    )
    (net (code "47") (name "Net-(LED32-DO)") (class "Default")
      (node (ref "LED32") (pin "3") (pinfunction "DO_3") (pintype "passive"))
      (node (ref "LED33") (pin "4") (pinfunction "DIN_4") (pintype "passive"))
      (node (ref "LED34") (pin "6") (pinfunction "BIN_6") (pintype "passive"))
    )
    (net (code "48") (name "Net-(LED33-DO)") (class "Default")
      (node (ref "LED33") (pin "3") (pinfunction "DO_3") (pintype "passive"))
      (node (ref "LED34") (pin "4") (pinfunction "DIN_4") (pintype "passive"))
      (node (ref "LED35") (pin "6") (pinfunction "BIN_6") (pintype "passive"))
    )
    (net (code "49") (name "Net-(LED34-DO)") (class "Default")
      (node (ref "LED34") (pin "3") (pinfunction "DO_3") (pintype "passive"))
      (node (ref "LED35") (pin "4") (pinfunction "DIN_4") (pintype "passive"))
      (node (ref "LED36") (pin "6") (pinfunction "BIN_6") (pintype "passive"))
    )
    (net (code "50") (name "Net-(LED37-DO)") (class "Default")
      (node (ref "LED37") (pin "3") (pinfunction "DO_3") (pintype "passive"))
      (node (ref "LED38") (pin "4") (pinfunction "DIN_4") (pintype "passive"))
      (node (ref "LED39") (pin "6") (pinfunction "BIN_6") (pintype "passive"))
    )
    (net (code "51") (name "Net-(LED38-DO)") (class "Default")
      (node (ref "LED38") (pin "3") (pinfunction "DO_3") (pintype "passive"))
      (node (ref "LED39") (pin "4") (pinfunction "DIN_4") (pintype "passive"))
      (node (ref "LED40") (pin "6") (pinfunction "BIN_6") (pintype "passive"))
    )
    (net (code "52") (name "Net-(LED39-DO)") (class "Default")
      (node (ref "LED39") (pin "3") (pinfunction "DO_3") (pintype "passive"))
      (node (ref "LED40") (pin "4") (pinfunction "DIN_4") (pintype "passive"))
      (node (ref "LED41") (pin "6") (pinfunction "BIN_6") (pintype "passive"))
    )
    (net (code "53") (name "Net-(LED40-DO)") (class "Default")
      (node (ref "LED40") (pin "3") (pinfunction "DO_3") (pintype "passive"))
      (node (ref "LED41") (pin "4") (pinfunction "DIN_4") (pintype "passive"))
      (node (ref "LED42") (pin "6") (pinfunction "BIN_6") (pintype "passive"))
    )
    (net (code "54") (name "Net-(LED43-DO)") (class "Default")
      (node (ref "LED43") (pin "3") (pinfunction "DO_3") (pintype "passive"))
      (node (ref "LED44") (pin "4") (pinfunction "DIN_4") (pintype "passive"))
      (node (ref "LED45") (pin "6") (pinfunction "BIN_6") (pintype "passive"))
    )
    (net (code "55") (name "Net-(LED44-DO)") (class "Default")
      (node (ref "LED44") (pin "3") (pinfunction "DO_3") (pintype "passive"))
      (node (ref "LED45") (pin "4") (pinfunction "DIN_4") (pintype "passive"))
      (node (ref "LED46") (pin "6") (pinfunction "BIN_6") (pintype "passive"))
    )
    (net (code "56") (name "Net-(LED45-DO)") (class "Default")
      (node (ref "LED45") (pin "3") (pinfunction "DO_3") (pintype "passive"))
      (node (ref "LED46") (pin "4") (pinfunction "DIN_4") (pintype "passive"))
      (node (ref "LED47") (pin "6") (pinfunction "BIN_6") (pintype "passive"))
    )
    (net (code "57") (name "Net-(LED46-DO)") (class "Default")
      (node (ref "LED46") (pin "3") (pinfunction "DO_3") (pintype "passive"))
      (node (ref "LED47") (pin "4") (pinfunction "DIN_4") (pintype "passive"))
      (node (ref "LED48") (pin "6") (pinfunction "BIN_6") (pintype "passive"))
    )
    (net (code "58") (name "Net-(LED49-DO)") (class "Default")
      (node (ref "LED49") (pin "3") (pinfunction "DO_3") (pintype "passive"))
      (node (ref "LED50") (pin "4") (pinfunction "DIN_4") (pintype "passive"))
      (node (ref "LED51") (pin "6") (pinfunction "BIN_6") (pintype "passive"))
    )
    (net (code "59") (name "Net-(LED50-DO)") (class "Default")
      (node (ref "LED50") (pin "3") (pinfunction "DO_3") (pintype "passive"))
      (node (ref "LED51") (pin "4") (pinfunction "DIN_4") (pintype "passive"))
      (node (ref "LED52") (pin "6") (pinfunction "BIN_6") (pintype "passive"))
    )
    (net (code "60") (name "Net-(LED51-DO)") (class "Default")
      (node (ref "LED51") (pin "3") (pinfunction "DO_3") (pintype "passive"))
      (node (ref "LED52") (pin "4") (pinfunction "DIN_4") (pintype "passive"))
      (node (ref "LED53") (pin "6") (pinfunction "BIN_6") (pintype "passive"))
    )
    (net (code "61") (name "Net-(LED52-DO)") (class "Default")
      (node (ref "LED52") (pin "3") (pinfunction "DO_3") (pintype "passive"))
      (node (ref "LED53") (pin "4") (pinfunction "DIN_4") (pintype "passive"))
      (node (ref "LED54") (pin "6") (pinfunction "BIN_6") (pintype "passive"))
    )
    (net (code "62") (name "Net-(LED55-DO)") (class "Default")
      (node (ref "LED55") (pin "3") (pinfunction "DO_3") (pintype "passive"))
      (node (ref "LED56") (pin "4") (pinfunction "DIN_4") (pintype "passive"))
      (node (ref "LED57") (pin "6") (pinfunction "BIN_6") (pintype "passive"))
    )
    (net (code "63") (name "Net-(LED56-DO)") (class "Default")
      (node (ref "LED56") (pin "3") (pinfunction "DO_3") (pintype "passive"))
      (node (ref "LED57") (pin "4") (pinfunction "DIN_4") (pintype "passive"))
      (node (ref "LED58") (pin "6") (pinfunction "BIN_6") (pintype "passive"))
    )
    (net (code "64") (name "Net-(LED57-DO)") (class "Default")
      (node (ref "LED57") (pin "3") (pinfunction "DO_3") (pintype "passive"))
      (node (ref "LED58") (pin "4") (pinfunction "DIN_4") (pintype "passive"))
      (node (ref "LED59") (pin "6") (pinfunction "BIN_6") (pintype "passive"))
    )
    (net (code "65") (name "Net-(LED58-DO)") (class "Default")
      (node (ref "LED58") (pin "3") (pinfunction "DO_3") (pintype "passive"))
      (node (ref "LED59") (pin "4") (pinfunction "DIN_4") (pintype "passive"))
      (node (ref "LED60") (pin "6") (pinfunction "BIN_6") (pintype "passive"))
    )
    (net (code "66") (name "Net-(LED61-DO)") (class "Default")
      (node (ref "LED61") (pin "3") (pinfunction "DO_3") (pintype "passive"))
      (node (ref "LED62") (pin "4") (pinfunction "DIN_4") (pintype "passive"))
      (node (ref "LED63") (pin "6") (pinfunction "BIN_6") (pintype "passive"))
    )
    (net (code "67") (name "Net-(LED62-DO)") (class "Default")
      (node (ref "LED62") (pin "3") (pinfunction "DO_3") (pintype "passive"))
      (node (ref "LED63") (pin "4") (pinfunction "DIN_4") (pintype "passive"))
      (node (ref "LED64") (pin "6") (pinfunction "BIN_6") (pintype "passive"))
    )
    (net (code "68") (name "Net-(LED63-DO)") (class "Default")
      (node (ref "LED63") (pin "3") (pinfunction "DO_3") (pintype "passive"))
      (node (ref "LED64") (pin "4") (pinfunction "DIN_4") (pintype "passive"))
      (node (ref "LED65") (pin "6") (pinfunction "BIN_6") (pintype "passive"))
    )
    (net (code "69") (name "Net-(LED64-DO)") (class "Default")
      (node (ref "LED64") (pin "3") (pinfunction "DO_3") (pintype "passive"))
      (node (ref "LED65") (pin "4") (pinfunction "DIN_4") (pintype "passive"))
      (node (ref "LED66") (pin "6") (pinfunction "BIN_6") (pintype "passive"))
    )
    (net (code "70") (name "Net-(LED67-DO)") (class "Default")
      (node (ref "LED67") (pin "3") (pinfunction "DO_3") (pintype "passive"))
      (node (ref "LED68") (pin "4") (pinfunction "DIN_4") (pintype "passive"))
      (node (ref "LED69") (pin "6") (pinfunction "BIN_6") (pintype "passive"))
    )
    (net (code "71") (name "Net-(LED68-DO)") (class "Default")
      (node (ref "LED68") (pin "3") (pinfunction "DO_3") (pintype "passive"))
      (node (ref "LED69") (pin "4") (pinfunction "DIN_4") (pintype "passive"))
      (node (ref "LED70") (pin "6") (pinfunction "BIN_6") (pintype "passive"))
    )
    (net (code "72") (name "Net-(LED69-DO)") (class "Default")
      (node (ref "LED69") (pin "3") (pinfunction "DO_3") (pintype "passive"))
      (node (ref "LED70") (pin "4") (pinfunction "DIN_4") (pintype "passive"))
      (node (ref "LED71") (pin "6") (pinfunction "BIN_6") (pintype "passive"))
    )
    (net (code "73") (name "Net-(LED70-DO)") (class "Default")
      (node (ref "LED70") (pin "3") (pinfunction "DO_3") (pintype "passive"))
      (node (ref "LED71") (pin "4") (pinfunction "DIN_4") (pintype "passive"))
      (node (ref "LED72") (pin "6") (pinfunction "BIN_6") (pintype "passive"))
    )
    (net (code "74") (name "Net-(LED73-DO)") (class "Default")
      (node (ref "LED73") (pin "3") (pinfunction "DO_3") (pintype "passive"))
      (node (ref "LED74") (pin "4") (pinfunction "DIN_4") (pintype "passive"))
      (node (ref "LED75") (pin "6") (pinfunction "BIN_6") (pintype "passive"))
    )
    (net (code "75") (name "Net-(LED74-DO)") (class "Default")
      (node (ref "LED74") (pin "3") (pinfunction "DO_3") (pintype "passive"))
      (node (ref "LED75") (pin "4") (pinfunction "DIN_4") (pintype "passive"))
      (node (ref "LED76") (pin "6") (pinfunction "BIN_6") (pintype "passive"))
    )
    (net (code "76") (name "Net-(LED75-DO)") (class "Default")
      (node (ref "LED75") (pin "3") (pinfunction "DO_3") (pintype "passive"))
      (node (ref "LED76") (pin "4") (pinfunction "DIN_4") (pintype "passive"))
      (node (ref "LED77") (pin "6") (pinfunction "BIN_6") (pintype "passive"))
    )
    (net (code "77") (name "Net-(LED76-DO)") (class "Default")
      (node (ref "LED76") (pin "3") (pinfunction "DO_3") (pintype "passive"))
      (node (ref "LED77") (pin "4") (pinfunction "DIN_4") (pintype "passive"))
      (node (ref "LED78") (pin "6") (pinfunction "BIN_6") (pintype "passive"))
    )
    (net (code "78") (name "Net-(LED79-DO)") (class "Default")
      (node (ref "LED79") (pin "3") (pinfunction "DO_3") (pintype "passive"))
      (node (ref "LED80") (pin "4") (pinfunction "DIN_4") (pintype "passive"))
      (node (ref "LED81") (pin "6") (pinfunction "BIN_6") (pintype "passive"))
    )
    (net (code "79") (name "Net-(LED80-DO)") (class "Default")
      (node (ref "LED80") (pin "3") (pinfunction "DO_3") (pintype "passive"))
      (node (ref "LED81") (pin "4") (pinfunction "DIN_4") (pintype "passive"))
      (node (ref "LED82") (pin "6") (pinfunction "BIN_6") (pintype "passive"))
    )
    (net (code "80") (name "Net-(LED81-DO)") (class "Default")
      (node (ref "LED81") (pin "3") (pinfunction "DO_3") (pintype "passive"))
      (node (ref "LED82") (pin "4") (pinfunction "DIN_4") (pintype "passive"))
      (node (ref "LED83") (pin "6") (pinfunction "BIN_6") (pintype "passive"))
    )
    (net (code "81") (name "Net-(LED82-DO)") (class "Default")
      (node (ref "LED82") (pin "3") (pinfunction "DO_3") (pintype "passive"))
      (node (ref "LED83") (pin "4") (pinfunction "DIN_4") (pintype "passive"))
      (node (ref "LED84") (pin "6") (pinfunction "BIN_6") (pintype "passive"))
    )
    (net (code "82") (name "VCC") (class "Default")
      (node (ref "JP1") (pin "1") (pinfunction "1_1") (pintype "passive"))
      (node (ref "LED10") (pin "2") (pinfunction "VDD_2") (pintype "passive"))
      (node (ref "LED11") (pin "2") (pinfunction "VDD_2") (pintype "passive"))
      (node (ref "LED12") (pin "2") (pinfunction "VDD_2") (pintype "passive"))
      (node (ref "LED13") (pin "2") (pinfunction "VDD_2") (pintype "passive"))
      (node (ref "LED14") (pin "2") (pinfunction "VDD_2") (pintype "passive"))
      (node (ref "LED15") (pin "2") (pinfunction "VDD_2") (pintype "passive"))
      (node (ref "LED16") (pin "2") (pinfunction "VDD_2") (pintype "passive"))
      (node (ref "LED17") (pin "2") (pinfunction "VDD_2") (pintype "passive"))
      (node (ref "LED18") (pin "2") (pinfunction "VDD_2") (pintype "passive"))
      (node (ref "LED19") (pin "2") (pinfunction "VDD_2") (pintype "passive"))
      (node (ref "LED20") (pin "2") (pinfunction "VDD_2") (pintype "passive"))
      (node (ref "LED21") (pin "2") (pinfunction "VDD_2") (pintype "passive"))
      (node (ref "LED22") (pin "2") (pinfunction "VDD_2") (pintype "passive"))
      (node (ref "LED23") (pin "2") (pinfunction "VDD_2") (pintype "passive"))
      (node (ref "LED24") (pin "2") (pinfunction "VDD_2") (pintype "passive"))
      (node (ref "LED25") (pin "2") (pinfunction "VDD_2") (pintype "passive"))
      (node (ref "LED26") (pin "2") (pinfunction "VDD_2") (pintype "passive"))
      (node (ref "LED27") (pin "2") (pinfunction "VDD_2") (pintype "passive"))
      (node (ref "LED28") (pin "2") (pinfunction "VDD_2") (pintype "passive"))
      (node (ref "LED29") (pin "2") (pinfunction "VDD_2") (pintype "passive"))
      (node (ref "LED30") (pin "2") (pinfunction "VDD_2") (pintype "passive"))
      (node (ref "LED31") (pin "2") (pinfunction "VDD_2") (pintype "passive"))
      (node (ref "LED32") (pin "2") (pinfunction "VDD_2") (pintype "passive"))
      (node (ref "LED33") (pin "2") (pinfunction "VDD_2") (pintype "passive"))
      (node (ref "LED34") (pin "2") (pinfunction "VDD_2") (pintype "passive"))
      (node (ref "LED35") (pin "2") (pinfunction "VDD_2") (pintype "passive"))
      (node (ref "LED36") (pin "2") (pinfunction "VDD_2") (pintype "passive"))
      (node (ref "LED37") (pin "2") (pinfunction "VDD_2") (pintype "passive"))
      (node (ref "LED38") (pin "2") (pinfunction "VDD_2") (pintype "passive"))
      (node (ref "LED39") (pin "2") (pinfunction "VDD_2") (pintype "passive"))
      (node (ref "LED40") (pin "2") (pinfunction "VDD_2") (pintype "passive"))
      (node (ref "LED41") (pin "2") (pinfunction "VDD_2") (pintype "passive"))
      (node (ref "LED42") (pin "2") (pinfunction "VDD_2") (pintype "passive"))
      (node (ref "LED43") (pin "2") (pinfunction "VDD_2") (pintype "passive"))
      (node (ref "LED44") (pin "2") (pinfunction "VDD_2") (pintype "passive"))
      (node (ref "LED45") (pin "2") (pinfunction "VDD_2") (pintype "passive"))
      (node (ref "LED46") (pin "2") (pinfunction "VDD_2") (pintype "passive"))
      (node (ref "LED47") (pin "2") (pinfunction "VDD_2") (pintype "passive"))
      (node (ref "LED48") (pin "2") (pinfunction "VDD_2") (pintype "passive"))
      (node (ref "LED49") (pin "2") (pinfunction "VDD_2") (pintype "passive"))
      (node (ref "LED50") (pin "2") (pinfunction "VDD_2") (pintype "passive"))
      (node (ref "LED51") (pin "2") (pinfunction "VDD_2") (pintype "passive"))
      (node (ref "LED52") (pin "2") (pinfunction "VDD_2") (pintype "passive"))
      (node (ref "LED53") (pin "2") (pinfunction "VDD_2") (pintype "passive"))
      (node (ref "LED54") (pin "2") (pinfunction "VDD_2") (pintype "passive"))
      (node (ref "LED55") (pin "2") (pinfunction "VDD_2") (pintype "passive"))
      (node (ref "LED56") (pin "2") (pinfunction "VDD_2") (pintype "passive"))
      (node (ref "LED57") (pin "2") (pinfunction "VDD_2") (pintype "passive"))
      (node (ref "LED58") (pin "2") (pinfunction "VDD_2") (pintype "passive"))
      (node (ref "LED59") (pin "2") (pinfunction "VDD_2") (pintype "passive"))
      (node (ref "LED60") (pin "2") (pinfunction "VDD_2") (pintype "passive"))
      (node (ref "LED61") (pin "2") (pinfunction "VDD_2") (pintype "passive"))
      (node (ref "LED62") (pin "2") (pinfunction "VDD_2") (pintype "passive"))
      (node (ref "LED63") (pin "2") (pinfunction "VDD_2") (pintype "passive"))
      (node (ref "LED64") (pin "2") (pinfunction "VDD_2") (pintype "passive"))
      (node (ref "LED65") (pin "2") (pinfunction "VDD_2") (pintype "passive"))
      (node (ref "LED66") (pin "2") (pinfunction "VDD_2") (pintype "passive"))
      (node (ref "LED67") (pin "2") (pinfunction "VDD_2") (pintype "passive"))
      (node (ref "LED68") (pin "2") (pinfunction "VDD_2") (pintype "passive"))
      (node (ref "LED69") (pin "2") (pinfunction "VDD_2") (pintype "passive"))
      (node (ref "LED7") (pin "2") (pinfunction "VDD_2") (pintype "passive"))
      (node (ref "LED70") (pin "2") (pinfunction "VDD_2") (pintype "passive"))
      (node (ref "LED71") (pin "2") (pinfunction "VDD_2") (pintype "passive"))
      (node (ref "LED72") (pin "2") (pinfunction "VDD_2") (pintype "passive"))
      (node (ref "LED73") (pin "2") (pinfunction "VDD_2") (pintype "passive"))
      (node (ref "LED74") (pin "2") (pinfunction "VDD_2") (pintype "passive"))
      (node (ref "LED75") (pin "2") (pinfunction "VDD_2") (pintype "passive"))
      (node (ref "LED76") (pin "2") (pinfunction "VDD_2") (pintype "passive"))
      (node (ref "LED77") (pin "2") (pinfunction "VDD_2") (pintype "passive"))
      (node (ref "LED78") (pin "2") (pinfunction "VDD_2") (pintype "passive"))
      (node (ref "LED79") (pin "2") (pinfunction "VDD_2") (pintype "passive"))
      (node (ref "LED8") (pin "2") (pinfunction "VDD_2") (pintype "passive"))
      (node (ref "LED80") (pin "2") (pinfunction "VDD_2") (pintype "passive"))
      (node (ref "LED81") (pin "2") (pinfunction "VDD_2") (pintype "passive"))
      (node (ref "LED82") (pin "2") (pinfunction "VDD_2") (pintype "passive"))
      (node (ref "LED83") (pin "2") (pinfunction "VDD_2") (pintype "passive"))
      (node (ref "LED84") (pin "2") (pinfunction "VDD_2") (pintype "passive"))
      (node (ref "LED9") (pin "2") (pinfunction "VDD_2") (pintype "passive"))
      (node (ref "X1") (pin "3") (pinfunction "VCC_3") (pintype "bidirectional"))
    )
    (net (code "83") (name "unconnected-(LED7-VCC-Pad1)") (class "Default")
      (node (ref "LED7") (pin "1") (pinfunction "VCC_1") (pintype "passive"))
    )
    (net (code "84") (name "unconnected-(LED8-VCC-Pad1)") (class "Default")
      (node (ref "LED8") (pin "1") (pinfunction "VCC_1") (pintype "passive"))
    )
    (net (code "85") (name "unconnected-(LED9-VCC-Pad1)") (class "Default")
      (node (ref "LED9") (pin "1") (pinfunction "VCC_1") (pintype "passive"))
    )
    (net (code "86") (name "unconnected-(LED10-VCC-Pad1)") (class "Default")
      (node (ref "LED10") (pin "1") (pinfunction "VCC_1") (pintype "passive"))
    )
    (net (code "87") (name "unconnected-(LED11-VCC-Pad1)") (class "Default")
      (node (ref "LED11") (pin "1") (pinfunction "VCC_1") (pintype "passive"))
    )
    (net (code "88") (name "unconnected-(LED12-VCC-Pad1)") (class "Default")
      (node (ref "LED12") (pin "1") (pinfunction "VCC_1") (pintype "passive"))
    )
    (net (code "89") (name "unconnected-(LED13-VCC-Pad1)") (class "Default")
      (node (ref "LED13") (pin "1") (pinfunction "VCC_1") (pintype "passive"))
    )
    (net (code "90") (name "unconnected-(LED14-VCC-Pad1)") (class "Default")
      (node (ref "LED14") (pin "1") (pinfunction "VCC_1") (pintype "passive"))
    )
    (net (code "91") (name "unconnected-(LED15-VCC-Pad1)") (class "Default")
      (node (ref "LED15") (pin "1") (pinfunction "VCC_1") (pintype "passive"))
    )
    (net (code "92") (name "unconnected-(LED16-VCC-Pad1)") (class "Default")
      (node (ref "LED16") (pin "1") (pinfunction "VCC_1") (pintype "passive"))
    )
    (net (code "93") (name "unconnected-(LED17-VCC-Pad1)") (class "Default")
      (node (ref "LED17") (pin "1") (pinfunction "VCC_1") (pintype "passive"))
    )
    (net (code "94") (name "unconnected-(LED18-VCC-Pad1)") (class "Default")
      (node (ref "LED18") (pin "1") (pinfunction "VCC_1") (pintype "passive"))
    )
    (net (code "95") (name "unconnected-(LED19-VCC-Pad1)") (class "Default")
      (node (ref "LED19") (pin "1") (pinfunction "VCC_1") (pintype "passive"))
    )
    (net (code "96") (name "unconnected-(LED20-VCC-Pad1)") (class "Default")
      (node (ref "LED20") (pin "1") (pinfunction "VCC_1") (pintype "passive"))
    )
    (net (code "97") (name "unconnected-(LED21-VCC-Pad1)") (class "Default")
      (node (ref "LED21") (pin "1") (pinfunction "VCC_1") (pintype "passive"))
    )
    (net (code "98") (name "unconnected-(LED22-VCC-Pad1)") (class "Default")
      (node (ref "LED22") (pin "1") (pinfunction "VCC_1") (pintype "passive"))
    )
    (net (code "99") (name "unconnected-(LED23-VCC-Pad1)") (class "Default")
      (node (ref "LED23") (pin "1") (pinfunction "VCC_1") (pintype "passive"))
    )
    (net (code "100") (name "unconnected-(LED24-VCC-Pad1)") (class "Default")
      (node (ref "LED24") (pin "1") (pinfunction "VCC_1") (pintype "passive"))
    )
    (net (code "101") (name "unconnected-(LED25-VCC-Pad1)") (class "Default")
      (node (ref "LED25") (pin "1") (pinfunction "VCC_1") (pintype "passive"))
    )
    (net (code "102") (name "unconnected-(LED26-VCC-Pad1)") (class "Default")
      (node (ref "LED26") (pin "1") (pinfunction "VCC_1") (pintype "passive"))
    )
    (net (code "103") (name "unconnected-(LED27-VCC-Pad1)") (class "Default")
      (node (ref "LED27") (pin "1") (pinfunction "VCC_1") (pintype "passive"))
    )
    (net (code "104") (name "unconnected-(LED28-VCC-Pad1)") (class "Default")
      (node (ref "LED28") (pin "1") (pinfunction "VCC_1") (pintype "passive"))
    )
    (net (code "105") (name "unconnected-(LED29-VCC-Pad1)") (class "Default")
      (node (ref "LED29") (pin "1") (pinfunction "VCC_1") (pintype "passive"))
    )
    (net (code "106") (name "unconnected-(LED30-VCC-Pad1)") (class "Default")
      (node (ref "LED30") (pin "1") (pinfunction "VCC_1") (pintype "passive"))
    )
    (net (code "107") (name "unconnected-(LED31-VCC-Pad1)") (class "Default")
      (node (ref "LED31") (pin "1") (pinfunction "VCC_1") (pintype "passive"))
    )
    (net (code "108") (name "unconnected-(LED32-VCC-Pad1)") (class "Default")
      (node (ref "LED32") (pin "1") (pinfunction "VCC_1") (pintype "passive"))
    )
    (net (code "109") (name "unconnected-(LED33-VCC-Pad1)") (class "Default")
      (node (ref "LED33") (pin "1") (pinfunction "VCC_1") (pintype "passive"))
    )
    (net (code "110") (name "unconnected-(LED34-VCC-Pad1)") (class "Default")
      (node (ref "LED34") (pin "1") (pinfunction "VCC_1") (pintype "passive"))
    )
    (net (code "111") (name "unconnected-(LED35-VCC-Pad1)") (class "Default")
      (node (ref "LED35") (pin "1") (pinfunction "VCC_1") (pintype "passive"))
    )
    (net (code "112") (name "unconnected-(LED36-VCC-Pad1)") (class "Default")
      (node (ref "LED36") (pin "1") (pinfunction "VCC_1") (pintype "passive"))
    )
    (net (code "113") (name "unconnected-(LED37-VCC-Pad1)") (class "Default")
      (node (ref "LED37") (pin "1") (pinfunction "VCC_1") (pintype "passive"))
    )
    (net (code "114") (name "unconnected-(LED38-VCC-Pad1)") (class "Default")
      (node (ref "LED38") (pin "1") (pinfunction "VCC_1") (pintype "passive"))
    )
    (net (code "115") (name "unconnected-(LED39-VCC-Pad1)") (class "Default")
      (node (ref "LED39") (pin "1") (pinfunction "VCC_1") (pintype "passive"))
    )
    (net (code "116") (name "unconnected-(LED40-VCC-Pad1)") (class "Default")
      (node (ref "LED40") (pin "1") (pinfunction "VCC_1") (pintype "passive"))
    )
    (net (code "117") (name "unconnected-(LED41-VCC-Pad1)") (class "Default")
      (node (ref "LED41") (pin "1") (pinfunction "VCC_1") (pintype "passive"))
    )
    (net (code "118") (name "unconnected-(LED42-VCC-Pad1)") (class "Default")
      (node (ref "LED42") (pin "1") (pinfunction "VCC_1") (pintype "passive"))
    )
    (net (code "119") (name "unconnected-(LED43-VCC-Pad1)") (class "Default")
      (node (ref "LED43") (pin "1") (pinfunction "VCC_1") (pintype "passive"))
    )
    (net (code "120") (name "unconnected-(LED44-VCC-Pad1)") (class "Default")
      (node (ref "LED44") (pin "1") (pinfunction "VCC_1") (pintype "passive"))
    )
    (net (code "121") (name "unconnected-(LED45-VCC-Pad1)") (class "Default")
      (node (ref "LED45") (pin "1") (pinfunction "VCC_1") (pintype "passive"))
    )
    (net (code "122") (name "unconnected-(LED46-VCC-Pad1)") (class "Default")
      (node (ref "LED46") (pin "1") (pinfunction "VCC_1") (pintype "passive"))
    )
    (net (code "123") (name "unconnected-(LED47-VCC-Pad1)") (class "Default")
      (node (ref "LED47") (pin "1") (pinfunction "VCC_1") (pintype "passive"))
    )
    (net (code "124") (name "unconnected-(LED48-VCC-Pad1)") (class "Default")
      (node (ref "LED48") (pin "1") (pinfunction "VCC_1") (pintype "passive"))
    )
    (net (code "125") (name "unconnected-(LED49-VCC-Pad1)") (class "Default")
      (node (ref "LED49") (pin "1") (pinfunction "VCC_1") (pintype "passive"))
    )
    (net (code "126") (name "unconnected-(LED50-VCC-Pad1)") (class "Default")
      (node (ref "LED50") (pin "1") (pinfunction "VCC_1") (pintype "passive"))
    )
    (net (code "127") (name "unconnected-(LED51-VCC-Pad1)") (class "Default")
      (node (ref "LED51") (pin "1") (pinfunction "VCC_1") (pintype "passive"))
    )
    (net (code "128") (name "unconnected-(LED52-VCC-Pad1)") (class "Default")
      (node (ref "LED52") (pin "1") (pinfunction "VCC_1") (pintype "passive"))
    )
    (net (code "129") (name "unconnected-(LED53-VCC-Pad1)") (class "Default")
      (node (ref "LED53") (pin "1") (pinfunction "VCC_1") (pintype "passive"))
    )
    (net (code "130") (name "unconnected-(LED54-VCC-Pad1)") (class "Default")
      (node (ref "LED54") (pin "1") (pinfunction "VCC_1") (pintype "passive"))
    )
    (net (code "131") (name "unconnected-(LED55-VCC-Pad1)") (class "Default")
      (node (ref "LED55") (pin "1") (pinfunction "VCC_1") (pintype "passive"))
    )
    (net (code "132") (name "unconnected-(LED56-VCC-Pad1)") (class "Default")
      (node (ref "LED56") (pin "1") (pinfunction "VCC_1") (pintype "passive"))
    )
    (net (code "133") (name "unconnected-(LED57-VCC-Pad1)") (class "Default")
      (node (ref "LED57") (pin "1") (pinfunction "VCC_1") (pintype "passive"))
    )
    (net (code "134") (name "unconnected-(LED58-VCC-Pad1)") (class "Default")
      (node (ref "LED58") (pin "1") (pinfunction "VCC_1") (pintype "passive"))
    )
    (net (code "135") (name "unconnected-(LED59-VCC-Pad1)") (class "Default")
      (node (ref "LED59") (pin "1") (pinfunction "VCC_1") (pintype "passive"))
    )
    (net (code "136") (name "unconnected-(LED60-VCC-Pad1)") (class "Default")
      (node (ref "LED60") (pin "1") (pinfunction "VCC_1") (pintype "passive"))
    )
    (net (code "137") (name "unconnected-(LED61-VCC-Pad1)") (class "Default")
      (node (ref "LED61") (pin "1") (pinfunction "VCC_1") (pintype "passive"))
    )
    (net (code "138") (name "unconnected-(LED62-VCC-Pad1)") (class "Default")
      (node (ref "LED62") (pin "1") (pinfunction "VCC_1") (pintype "passive"))
    )
    (net (code "139") (name "unconnected-(LED63-VCC-Pad1)") (class "Default")
      (node (ref "LED63") (pin "1") (pinfunction "VCC_1") (pintype "passive"))
    )
    (net (code "140") (name "unconnected-(LED64-VCC-Pad1)") (class "Default")
      (node (ref "LED64") (pin "1") (pinfunction "VCC_1") (pintype "passive"))
    )
    (net (code "141") (name "unconnected-(LED65-VCC-Pad1)") (class "Default")
      (node (ref "LED65") (pin "1") (pinfunction "VCC_1") (pintype "passive"))
    )
    (net (code "142") (name "unconnected-(LED66-VCC-Pad1)") (class "Default")
      (node (ref "LED66") (pin "1") (pinfunction "VCC_1") (pintype "passive"))
    )
    (net (code "143") (name "unconnected-(LED67-VCC-Pad1)") (class "Default")
      (node (ref "LED67") (pin "1") (pinfunction "VCC_1") (pintype "passive"))
    )
    (net (code "144") (name "unconnected-(LED68-VCC-Pad1)") (class "Default")
      (node (ref "LED68") (pin "1") (pinfunction "VCC_1") (pintype "passive"))
    )
    (net (code "145") (name "unconnected-(LED69-VCC-Pad1)") (class "Default")
      (node (ref "LED69") (pin "1") (pinfunction "VCC_1") (pintype "passive"))
    )
    (net (code "146") (name "unconnected-(LED70-VCC-Pad1)") (class "Default")
      (node (ref "LED70") (pin "1") (pinfunction "VCC_1") (pintype "passive"))
    )
    (net (code "147") (name "unconnected-(LED71-VCC-Pad1)") (class "Default")
      (node (ref "LED71") (pin "1") (pinfunction "VCC_1") (pintype "passive"))
    )
    (net (code "148") (name "unconnected-(LED72-VCC-Pad1)") (class "Default")
      (node (ref "LED72") (pin "1") (pinfunction "VCC_1") (pintype "passive"))
    )
    (net (code "149") (name "unconnected-(LED73-VCC-Pad1)") (class "Default")
      (node (ref "LED73") (pin "1") (pinfunction "VCC_1") (pintype "passive"))
    )
    (net (code "150") (name "unconnected-(LED74-VCC-Pad1)") (class "Default")
      (node (ref "LED74") (pin "1") (pinfunction "VCC_1") (pintype "passive"))
    )
    (net (code "151") (name "unconnected-(LED75-VCC-Pad1)") (class "Default")
      (node (ref "LED75") (pin "1") (pinfunction "VCC_1") (pintype "passive"))
    )
    (net (code "152") (name "unconnected-(LED76-VCC-Pad1)") (class "Default")
      (node (ref "LED76") (pin "1") (pinfunction "VCC_1") (pintype "passive"))
    )
    (net (code "153") (name "unconnected-(LED77-VCC-Pad1)") (class "Default")
      (node (ref "LED77") (pin "1") (pinfunction "VCC_1") (pintype "passive"))
    )
    (net (code "154") (name "unconnected-(LED78-VCC-Pad1)") (class "Default")
      (node (ref "LED78") (pin "1") (pinfunction "VCC_1") (pintype "passive"))
    )
    (net (code "155") (name "unconnected-(LED79-VCC-Pad1)") (class "Default")
      (node (ref "LED79") (pin "1") (pinfunction "VCC_1") (pintype "passive"))
    )
    (net (code "156") (name "unconnected-(LED80-VCC-Pad1)") (class "Default")
      (node (ref "LED80") (pin "1") (pinfunction "VCC_1") (pintype "passive"))
    )
    (net (code "157") (name "unconnected-(LED81-VCC-Pad1)") (class "Default")
      (node (ref "LED81") (pin "1") (pinfunction "VCC_1") (pintype "passive"))
    )
    (net (code "158") (name "unconnected-(LED82-VCC-Pad1)") (class "Default")
      (node (ref "LED82") (pin "1") (pinfunction "VCC_1") (pintype "passive"))
    )
    (net (code "159") (name "unconnected-(LED83-VCC-Pad1)") (class "Default")
      (node (ref "LED83") (pin "1") (pinfunction "VCC_1") (pintype "passive"))
    )
    (net (code "160") (name "unconnected-(LED84-VCC-Pad1)") (class "Default")
      (node (ref "LED84") (pin "1") (pinfunction "VCC_1") (pintype "passive"))
    )
  )
)
